# LEFT_MOTOR.net
KiCad netlist of a schematic drawn in Altium Designer
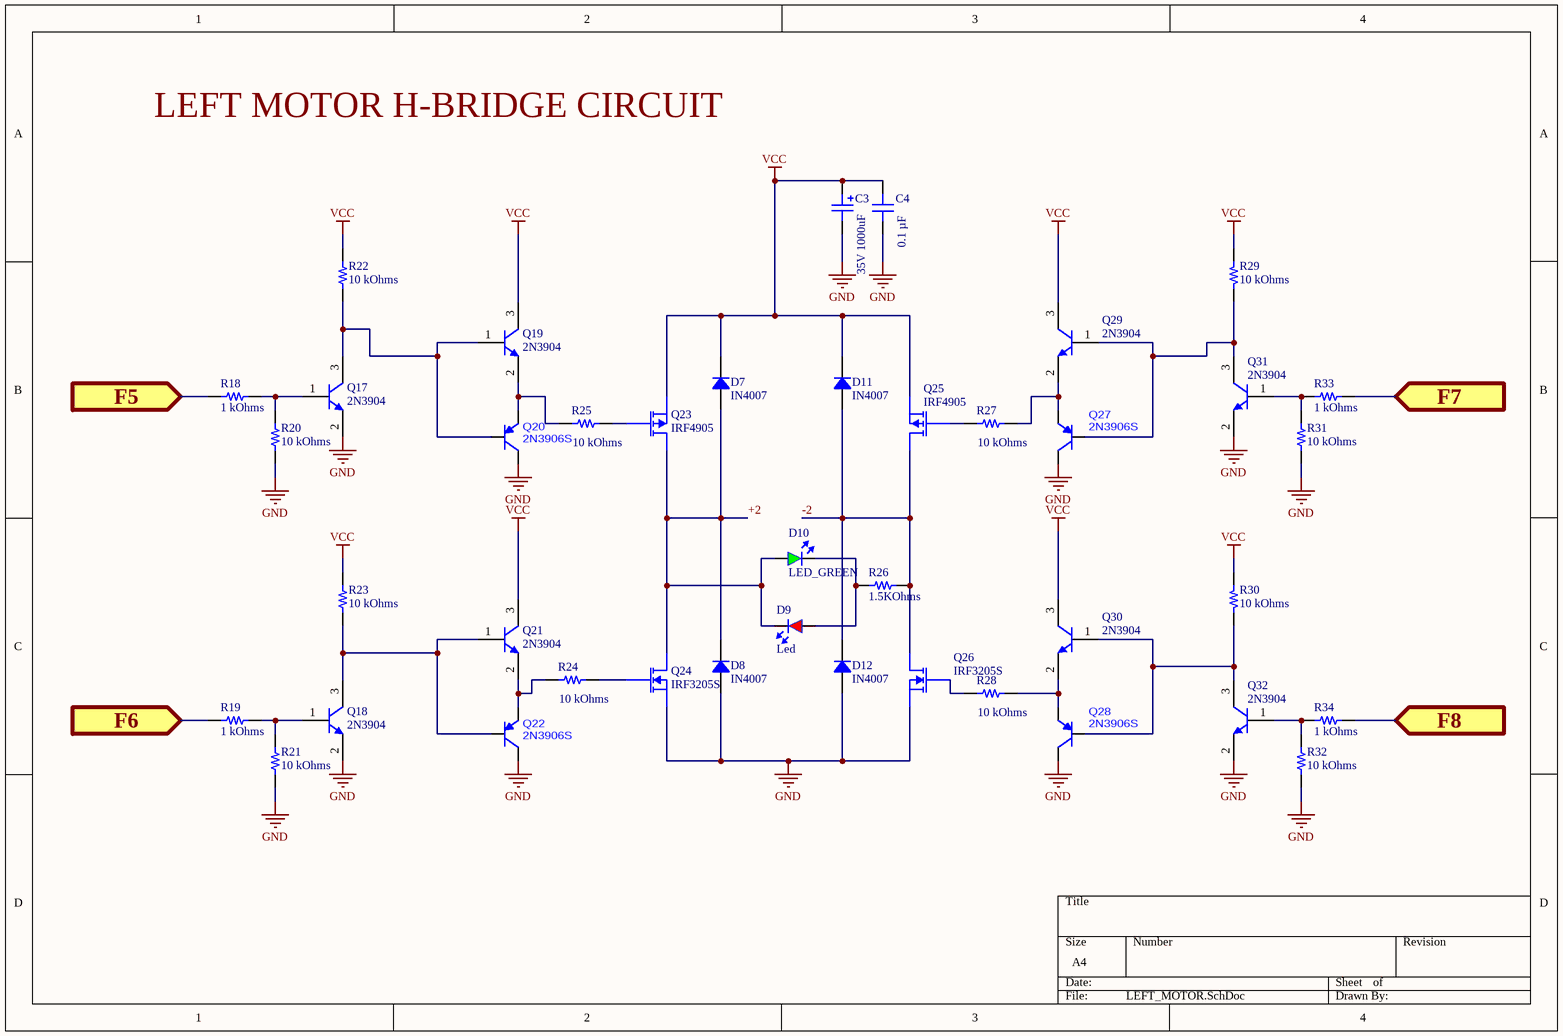
[diagram p0: LEFT_MOTOR.SchDoc]

(export (version "E")
  (design (tool "Eeschema 10.0.6"))
  (components
    (comp (ref "C3") (value "35V 1000uF") (footprint "35V 1000uF") (libsource (lib "AS") (part "35V 1000uF")))
    (comp (ref "C4")
      (value "0.1 µF")
      (footprint "CAP 1210_3225 - 1MM")
      (description "1210 50VDC 100NF 10% X7R(2R1) AE")
      (fields (field (name "PART NUMBER") "1210Y0500104KST") (field (name "MANUFACTURER") "Knowles Syfer"))
      (libsource (lib "Celestial Altium Library - altium_library") (part "Capacitor"))
    )
    (comp (ref "D7")
      (value "IN4007")
      (footprint "DO214AC SMA")
      (description "DIODE GEN PURP 50V 1A SMA")
      (fields (field (name "PART NUMBER") "RS1A") (field (name "MANUFACTURER") "ON Semiconductor"))
      (libsource (lib "Celestial Altium Library - altium_library") (part "Diode"))
    )
    (comp (ref "D8")
      (value "IN4007")
      (footprint "DO214AC SMA")
      (description "DIODE GEN PURP 50V 1A SMA")
      (fields (field (name "PART NUMBER") "RS1A") (field (name "MANUFACTURER") "ON Semiconductor"))
      (libsource (lib "Celestial Altium Library - altium_library") (part "Diode"))
    )
    (comp (ref "D9") (value "Led") (footprint "LED_RED") (libsource (lib "HBRIDGE") (part "LED_RED_1")))
    (comp (ref "D10")
      (value "LED_GREEN")
      (footprint "LED_GREEN")
      (libsource (lib "HBRIDGE") (part "LED_GREEN"))
    )
    (comp (ref "D11")
      (value "IN4007")
      (footprint "DO214AC SMA")
      (description "DIODE GEN PURP 50V 1A SMA")
      (fields (field (name "PART NUMBER") "RS1A") (field (name "MANUFACTURER") "ON Semiconductor"))
      (libsource (lib "Celestial Altium Library - altium_library") (part "Diode"))
    )
    (comp (ref "D12")
      (value "IN4007")
      (footprint "DO214AC SMA")
      (description "DIODE GEN PURP 50V 1A SMA")
      (fields (field (name "PART NUMBER") "RS1A") (field (name "MANUFACTURER") "ON Semiconductor"))
      (libsource (lib "Celestial Altium Library - altium_library") (part "Diode"))
    )
    (comp (ref "Q17")
      (value "2N3904")
      (footprint "DIODES SOT-23-3")
      (description "2N3904 Npn Smd Transistör Sot-23")
      (fields (field (name "PART NUMBER") "MMBT3904-7-F") (field (name "MANUFACTURER") "Diodes Incorporated"))
      (libsource (lib "Celestial Altium Library - altium_library") (part "DIODES INC NPN SOT-23-3"))
    )
    (comp (ref "Q18")
      (value "2N3904")
      (footprint "DIODES SOT-23-3")
      (description "2N3904 Npn Smd Transistör Sot-23")
      (fields (field (name "PART NUMBER") "MMBT3904-7-F") (field (name "MANUFACTURER") "Diodes Incorporated"))
      (libsource (lib "Celestial Altium Library - altium_library") (part "DIODES INC NPN SOT-23-3"))
    )
    (comp (ref "Q19")
      (value "2N3904")
      (footprint "DIODES SOT-23-3")
      (description "2N3904 Npn Smd Transistör Sot-23")
      (fields (field (name "PART NUMBER") "MMBT3904-7-F") (field (name "MANUFACTURER") "Diodes Incorporated"))
      (libsource (lib "Celestial Altium Library - altium_library") (part "DIODES INC NPN SOT-23-3"))
    )
    (comp (ref "Q20") (value "2N3906S") (footprint "SOT23-3") (libsource (lib "HBRIDGE") (part "2N3906S")))
    (comp (ref "Q21")
      (value "2N3904")
      (footprint "DIODES SOT-23-3")
      (description "2N3904 Npn Smd Transistör Sot-23")
      (fields (field (name "PART NUMBER") "MMBT3904-7-F") (field (name "MANUFACTURER") "Diodes Incorporated"))
      (libsource (lib "Celestial Altium Library - altium_library") (part "DIODES INC NPN SOT-23-3"))
    )
    (comp (ref "Q22") (value "2N3906S") (footprint "SOT23-3") (libsource (lib "HBRIDGE") (part "2N3906S")))
    (comp (ref "Q23") (value "IRF4905") (footprint "IRF4905") (libsource (lib "AS") (part "IRF4905")))
    (comp (ref "Q24") (value "IRF3205S") (footprint "IRF3205S") (libsource (lib "HBRIDGE") (part "IRF3205S")))
    (comp (ref "Q25") (value "IRF4905") (footprint "IRF4905") (libsource (lib "AS") (part "IRF4905")))
    (comp (ref "Q26") (value "IRF3205S") (footprint "IRF3205S") (libsource (lib "") (part "IRF3205S_1")))
    (comp (ref "Q27") (value "2N3906S") (footprint "SOT23-3") (libsource (lib "") (part "2N3906S_1")))
    (comp (ref "Q28") (value "2N3906S") (footprint "SOT23-3") (libsource (lib "") (part "2N3906S_1")))
    (comp (ref "Q29")
      (value "2N3904")
      (footprint "DIODES SOT-23-3")
      (description "2N3904 Npn Smd Transistör Sot-23")
      (fields (field (name "PART NUMBER") "MMBT3904-7-F") (field (name "MANUFACTURER") "Diodes Incorporated"))
      (libsource (lib "Celestial Altium Library - altium_library") (part "DIODES INC NPN SOT-23-3"))
    )
    (comp (ref "Q30")
      (value "2N3904")
      (footprint "DIODES SOT-23-3")
      (description "2N3904 Npn Smd Transistör Sot-23")
      (fields (field (name "PART NUMBER") "MMBT3904-7-F") (field (name "MANUFACTURER") "Diodes Incorporated"))
      (libsource (lib "Celestial Altium Library - altium_library") (part "DIODES INC NPN SOT-23-3"))
    )
    (comp (ref "Q31")
      (value "2N3904")
      (footprint "DIODES SOT-23-3")
      (description "2N3904 Npn Smd Transistör Sot-23")
      (fields (field (name "PART NUMBER") "MMBT3904-7-F") (field (name "MANUFACTURER") "Diodes Incorporated"))
      (libsource (lib "Celestial Altium Library - altium_library") (part "DIODES INC NPN SOT-23-3"))
    )
    (comp (ref "Q32")
      (value "2N3904")
      (footprint "DIODES SOT-23-3")
      (description "2N3904 Npn Smd Transistör Sot-23")
      (fields (field (name "PART NUMBER") "MMBT3904-7-F") (field (name "MANUFACTURER") "Diodes Incorporated"))
      (libsource (lib "Celestial Altium Library - altium_library") (part "DIODES INC NPN SOT-23-3"))
    )
    (comp (ref "R18")
      (value "1 kOhms")
      (footprint "RES 1206_3216")
      (description "RES 1K OHM 0.1% 1/8W 1206")
      (fields
        (field (name "PART NUMBER") "RNCS1206BKE1K00")
        (field (name "MANUFACTURER") "Stackpole Electronics Inc")
      )
      (libsource (lib "Celestial Altium Library - altium_library") (part "Resistor"))
    )
    (comp (ref "R19")
      (value "1 kOhms")
      (footprint "RES 1206_3216")
      (description "RES 1K OHM 0.1% 1/8W 1206")
      (fields
        (field (name "PART NUMBER") "RNCS1206BKE1K00")
        (field (name "MANUFACTURER") "Stackpole Electronics Inc")
      )
      (libsource (lib "Celestial Altium Library - altium_library") (part "Resistor"))
    )
    (comp (ref "R20")
      (value "10 kOhms")
      (footprint "RES 1206_3216")
      (description "RES SMD 10K OHM 1% 1/4W 1206")
      (fields
        (field (name "PART NUMBER") "CRG1206F10K")
        (field (name "MANUFACTURER") "TE Connectivity Passive Product")
      )
      (libsource (lib "Celestial Altium Library - altium_library") (part "Resistor"))
    )
    (comp (ref "R21")
      (value "10 kOhms")
      (footprint "RES 1206_3216")
      (description "RES SMD 10K OHM 1% 1/4W 1206")
      (fields
        (field (name "PART NUMBER") "CRG1206F10K")
        (field (name "MANUFACTURER") "TE Connectivity Passive Product")
      )
      (libsource (lib "Celestial Altium Library - altium_library") (part "Resistor"))
    )
    (comp (ref "R22")
      (value "10 kOhms")
      (footprint "RES 1210_3225")
      (description "RES SMD 10K OHM 5% 3/4W 1210")
      (fields (field (name "PART NUMBER") "CRCW121010K0JNEAHP") (field (name "MANUFACTURER") "Vishay Dale"))
      (libsource (lib "Celestial Altium Library - altium_library") (part "Resistor"))
    )
    (comp (ref "R23")
      (value "10 kOhms")
      (footprint "RES 1210_3225")
      (description "RES SMD 10K OHM 5% 3/4W 1210")
      (fields (field (name "PART NUMBER") "CRCW121010K0JNEAHP") (field (name "MANUFACTURER") "Vishay Dale"))
      (libsource (lib "Celestial Altium Library - altium_library") (part "Resistor"))
    )
    (comp (ref "R24")
      (value "10 kOhms")
      (footprint "RES 1210_3225")
      (description "RES 10K OHM 1% 1/2W 1210")
      (fields
        (field (name "PART NUMBER") "RMCF1210FT10K0")
        (field (name "MANUFACTURER") "Stackpole Electronics Inc")
      )
      (libsource (lib "Celestial Altium Library - altium_library") (part "Resistor"))
    )
    (comp (ref "R25")
      (value "10 kOhms")
      (footprint "RES 1210_3225")
      (description "RES 10K OHM 1% 1/2W 1210")
      (fields
        (field (name "PART NUMBER") "RMCF1210FT10K0")
        (field (name "MANUFACTURER") "Stackpole Electronics Inc")
      )
      (libsource (lib "Celestial Altium Library - altium_library") (part "Resistor"))
    )
    (comp (ref "R26")
      (value "1.5KOhms")
      (footprint "RES 1210_3225")
      (description "RES 10K OHM 1% 1/2W 1210")
      (fields
        (field (name "PART NUMBER") "RMCF1210FT10K0")
        (field (name "MANUFACTURER") "Stackpole Electronics Inc")
      )
      (libsource (lib "Celestial Altium Library - altium_library") (part "Resistor"))
    )
    (comp (ref "R27")
      (value "10 kOhms")
      (footprint "RES 1210_3225")
      (description "RES 10K OHM 1% 1/2W 1210")
      (fields
        (field (name "PART NUMBER") "RMCF1210FT10K0")
        (field (name "MANUFACTURER") "Stackpole Electronics Inc")
      )
      (libsource (lib "Celestial Altium Library - altium_library") (part "Resistor"))
    )
    (comp (ref "R28")
      (value "10 kOhms")
      (footprint "RES 1210_3225")
      (description "RES 10K OHM 1% 1/2W 1210")
      (fields
        (field (name "PART NUMBER") "RMCF1210FT10K0")
        (field (name "MANUFACTURER") "Stackpole Electronics Inc")
      )
      (libsource (lib "Celestial Altium Library - altium_library") (part "Resistor"))
    )
    (comp (ref "R29")
      (value "10 kOhms")
      (footprint "RES 1210_3225")
      (description "RES SMD 10K OHM 5% 3/4W 1210")
      (fields (field (name "PART NUMBER") "CRCW121010K0JNEAHP") (field (name "MANUFACTURER") "Vishay Dale"))
      (libsource (lib "Celestial Altium Library - altium_library") (part "Resistor"))
    )
    (comp (ref "R30")
      (value "10 kOhms")
      (footprint "RES 1210_3225")
      (description "RES SMD 10K OHM 5% 3/4W 1210")
      (fields (field (name "PART NUMBER") "CRCW121010K0JNEAHP") (field (name "MANUFACTURER") "Vishay Dale"))
      (libsource (lib "Celestial Altium Library - altium_library") (part "Resistor"))
    )
    (comp (ref "R31")
      (value "10 kOhms")
      (footprint "RES 1206_3216")
      (description "RES SMD 10K OHM 1% 1/4W 1206")
      (fields
        (field (name "PART NUMBER") "CRG1206F10K")
        (field (name "MANUFACTURER") "TE Connectivity Passive Product")
      )
      (libsource (lib "Celestial Altium Library - altium_library") (part "Resistor"))
    )
    (comp (ref "R32")
      (value "10 kOhms")
      (footprint "RES 1206_3216")
      (description "RES SMD 10K OHM 1% 1/4W 1206")
      (fields
        (field (name "PART NUMBER") "CRG1206F10K")
        (field (name "MANUFACTURER") "TE Connectivity Passive Product")
      )
      (libsource (lib "Celestial Altium Library - altium_library") (part "Resistor"))
    )
    (comp (ref "R33")
      (value "1 kOhms")
      (footprint "RES 1206_3216")
      (description "RES 1K OHM 0.1% 1/8W 1206")
      (fields
        (field (name "PART NUMBER") "RNCS1206BKE1K00")
        (field (name "MANUFACTURER") "Stackpole Electronics Inc")
      )
      (libsource (lib "Celestial Altium Library - altium_library") (part "Resistor"))
    )
    (comp (ref "R34")
      (value "1 kOhms")
      (footprint "RES 1206_3216")
      (description "RES 1K OHM 0.1% 1/8W 1206")
      (fields
        (field (name "PART NUMBER") "RNCS1206BKE1K00")
        (field (name "MANUFACTURER") "Stackpole Electronics Inc")
      )
      (libsource (lib "Celestial Altium Library - altium_library") (part "Resistor"))
    )
  )
  (nets
    (net (code "1") (name "/+2") (class "Default")
      (node (ref "D10") (pin "1") (pinfunction "IN_1") (pintype "passive"))
      (node (ref "D7") (pin "1") (pinfunction "1_1") (pintype "passive"))
      (node (ref "D8") (pin "2") (pinfunction "2_2") (pintype "passive"))
      (node (ref "D9") (pin "2") (pinfunction "OUT_2") (pintype "passive"))
      (node (ref "Q23") (pin "2") (pinfunction "D_2") (pintype "passive"))
      (node (ref "Q24") (pin "2") (pinfunction "D_2") (pintype "passive"))
    )
    (net (code "2") (name "/-2") (class "Default")
      (node (ref "D11") (pin "1") (pinfunction "1_1") (pintype "passive"))
      (node (ref "D12") (pin "2") (pinfunction "2_2") (pintype "passive"))
      (node (ref "Q25") (pin "2") (pinfunction "D_2") (pintype "passive"))
      (node (ref "Q26") (pin "2") (pinfunction "D_2") (pintype "passive"))
      (node (ref "R26") (pin "2") (pinfunction "2_2") (pintype "passive"))
    )
    (net (code "3") (name "/F5") (class "Default")
      (node (ref "R18") (pin "1") (pinfunction "1_1") (pintype "passive"))
    )
    (net (code "4") (name "/F6") (class "Default")
      (node (ref "R19") (pin "1") (pinfunction "1_1") (pintype "passive"))
    )
    (net (code "5") (name "/F7") (class "Default")
      (node (ref "R33") (pin "2") (pinfunction "2_2") (pintype "passive"))
    )
    (net (code "6") (name "/F8") (class "Default")
      (node (ref "R34") (pin "2") (pinfunction "2_2") (pintype "passive"))
    )
    (net (code "8") (name "GND") (class "Default")
      (node (ref "C3") (pin "2") (pinfunction "out_2") (pintype "passive"))
      (node (ref "C4") (pin "1") (pinfunction "1_1") (pintype "passive"))
      (node (ref "D12") (pin "1") (pinfunction "1_1") (pintype "passive"))
      (node (ref "D8") (pin "1") (pinfunction "1_1") (pintype "passive"))
      (node (ref "Q17") (pin "2") (pinfunction "E_2") (pintype "passive"))
      (node (ref "Q18") (pin "2") (pinfunction "E_2") (pintype "passive"))
      (node (ref "Q20") (pin "3") (pinfunction "C_3") (pintype "passive"))
      (node (ref "Q22") (pin "3") (pinfunction "C_3") (pintype "passive"))
      (node (ref "Q24") (pin "3") (pinfunction "S_3") (pintype "passive"))
      (node (ref "Q26") (pin "3") (pinfunction "S_3") (pintype "passive"))
      (node (ref "Q27") (pin "3") (pinfunction "C_3") (pintype "passive"))
      (node (ref "Q28") (pin "3") (pinfunction "C_3") (pintype "passive"))
      (node (ref "Q31") (pin "2") (pinfunction "E_2") (pintype "passive"))
      (node (ref "Q32") (pin "2") (pinfunction "E_2") (pintype "passive"))
      (node (ref "R20") (pin "1") (pinfunction "1_1") (pintype "passive"))
      (node (ref "R21") (pin "1") (pinfunction "1_1") (pintype "passive"))
      (node (ref "R31") (pin "1") (pinfunction "1_1") (pintype "passive"))
      (node (ref "R32") (pin "1") (pinfunction "1_1") (pintype "passive"))
    )
    (net (code "9") (name "Net-(D10-OUT)") (class "Default")
      (node (ref "D10") (pin "2") (pinfunction "OUT_2") (pintype "passive"))
      (node (ref "D9") (pin "1") (pinfunction "IN_1") (pintype "passive"))
      (node (ref "R26") (pin "1") (pinfunction "1_1") (pintype "passive"))
    )
    (net (code "10") (name "Net-(Q17-B)") (class "Default")
      (node (ref "Q17") (pin "1") (pinfunction "B_1") (pintype "passive"))
      (node (ref "R18") (pin "2") (pinfunction "2_2") (pintype "passive"))
      (node (ref "R20") (pin "2") (pinfunction "2_2") (pintype "passive"))
    )
    (net (code "11") (name "Net-(Q17-C)") (class "Default")
      (node (ref "Q17") (pin "3") (pinfunction "C_3") (pintype "passive"))
      (node (ref "Q19") (pin "1") (pinfunction "B_1") (pintype "passive"))
      (node (ref "Q20") (pin "1") (pinfunction "B_1") (pintype "passive"))
      (node (ref "R22") (pin "2") (pinfunction "2_2") (pintype "passive"))
    )
    (net (code "12") (name "Net-(Q18-B)") (class "Default")
      (node (ref "Q18") (pin "1") (pinfunction "B_1") (pintype "passive"))
      (node (ref "R19") (pin "2") (pinfunction "2_2") (pintype "passive"))
      (node (ref "R21") (pin "2") (pinfunction "2_2") (pintype "passive"))
    )
    (net (code "13") (name "Net-(Q18-C)") (class "Default")
      (node (ref "Q18") (pin "3") (pinfunction "C_3") (pintype "passive"))
      (node (ref "Q21") (pin "1") (pinfunction "B_1") (pintype "passive"))
      (node (ref "Q22") (pin "1") (pinfunction "B_1") (pintype "passive"))
      (node (ref "R23") (pin "2") (pinfunction "2_2") (pintype "passive"))
    )
    (net (code "14") (name "Net-(Q19-E)") (class "Default")
      (node (ref "Q19") (pin "2") (pinfunction "E_2") (pintype "passive"))
      (node (ref "Q20") (pin "2") (pinfunction "E_2") (pintype "passive"))
      (node (ref "R25") (pin "1") (pinfunction "1_1") (pintype "passive"))
    )
    (net (code "15") (name "Net-(Q21-E)") (class "Default")
      (node (ref "Q21") (pin "2") (pinfunction "E_2") (pintype "passive"))
      (node (ref "Q22") (pin "2") (pinfunction "E_2") (pintype "passive"))
      (node (ref "R24") (pin "1") (pinfunction "1_1") (pintype "passive"))
    )
    (net (code "16") (name "Net-(Q23-G)") (class "Default")
      (node (ref "Q23") (pin "1") (pinfunction "G_1") (pintype "passive"))
      (node (ref "R25") (pin "2") (pinfunction "2_2") (pintype "passive"))
    )
    (net (code "17") (name "Net-(Q24-G)") (class "Default")
      (node (ref "Q24") (pin "1") (pinfunction "G_1") (pintype "passive"))
      (node (ref "R24") (pin "2") (pinfunction "2_2") (pintype "passive"))
    )
    (net (code "18") (name "Net-(Q25-G)") (class "Default")
      (node (ref "Q25") (pin "1") (pinfunction "G_1") (pintype "passive"))
      (node (ref "R27") (pin "1") (pinfunction "1_1") (pintype "passive"))
    )
    (net (code "19") (name "Net-(Q26-G)") (class "Default")
      (node (ref "Q26") (pin "1") (pinfunction "G_1") (pintype "passive"))
      (node (ref "R28") (pin "1") (pinfunction "1_1") (pintype "passive"))
    )
    (net (code "20") (name "Net-(Q27-B)") (class "Default")
      (node (ref "Q27") (pin "1") (pinfunction "B_1") (pintype "passive"))
      (node (ref "Q29") (pin "1") (pinfunction "B_1") (pintype "passive"))
      (node (ref "Q31") (pin "3") (pinfunction "C_3") (pintype "passive"))
      (node (ref "R29") (pin "2") (pinfunction "2_2") (pintype "passive"))
    )
    (net (code "21") (name "Net-(Q27-E)") (class "Default")
      (node (ref "Q27") (pin "2") (pinfunction "E_2") (pintype "passive"))
      (node (ref "Q29") (pin "2") (pinfunction "E_2") (pintype "passive"))
      (node (ref "R27") (pin "2") (pinfunction "2_2") (pintype "passive"))
    )
    (net (code "22") (name "Net-(Q28-B)") (class "Default")
      (node (ref "Q28") (pin "1") (pinfunction "B_1") (pintype "passive"))
      (node (ref "Q30") (pin "1") (pinfunction "B_1") (pintype "passive"))
      (node (ref "Q32") (pin "3") (pinfunction "C_3") (pintype "passive"))
      (node (ref "R30") (pin "2") (pinfunction "2_2") (pintype "passive"))
    )
    (net (code "23") (name "Net-(Q28-E)") (class "Default")
      (node (ref "Q28") (pin "2") (pinfunction "E_2") (pintype "passive"))
      (node (ref "Q30") (pin "2") (pinfunction "E_2") (pintype "passive"))
      (node (ref "R28") (pin "2") (pinfunction "2_2") (pintype "passive"))
    )
    (net (code "24") (name "Net-(Q31-B)") (class "Default")
      (node (ref "Q31") (pin "1") (pinfunction "B_1") (pintype "passive"))
      (node (ref "R31") (pin "2") (pinfunction "2_2") (pintype "passive"))
      (node (ref "R33") (pin "1") (pinfunction "1_1") (pintype "passive"))
    )
    (net (code "25") (name "Net-(Q32-B)") (class "Default")
      (node (ref "Q32") (pin "1") (pinfunction "B_1") (pintype "passive"))
      (node (ref "R32") (pin "2") (pinfunction "2_2") (pintype "passive"))
      (node (ref "R34") (pin "1") (pinfunction "1_1") (pintype "passive"))
    )
    (net (code "26") (name "VCC") (class "Default")
      (node (ref "C3") (pin "1") (pinfunction "in_1") (pintype "passive"))
      (node (ref "C4") (pin "2") (pinfunction "2_2") (pintype "passive"))
      (node (ref "D11") (pin "2") (pinfunction "2_2") (pintype "passive"))
      (node (ref "D7") (pin "2") (pinfunction "2_2") (pintype "passive"))
      (node (ref "Q19") (pin "3") (pinfunction "C_3") (pintype "passive"))
      (node (ref "Q21") (pin "3") (pinfunction "C_3") (pintype "passive"))
      (node (ref "Q23") (pin "3") (pinfunction "S_3") (pintype "passive"))
      (node (ref "Q25") (pin "3") (pinfunction "S_3") (pintype "passive"))
      (node (ref "Q29") (pin "3") (pinfunction "C_3") (pintype "passive"))
      (node (ref "Q30") (pin "3") (pinfunction "C_3") (pintype "passive"))
      (node (ref "R22") (pin "1") (pinfunction "1_1") (pintype "passive"))
      (node (ref "R23") (pin "1") (pinfunction "1_1") (pintype "passive"))
      (node (ref "R29") (pin "1") (pinfunction "1_1") (pintype "passive"))
      (node (ref "R30") (pin "1") (pinfunction "1_1") (pintype "passive"))
    )
  )
)
